# Mainboard.net
KiCad netlist of a schematic drawn in EAGLE
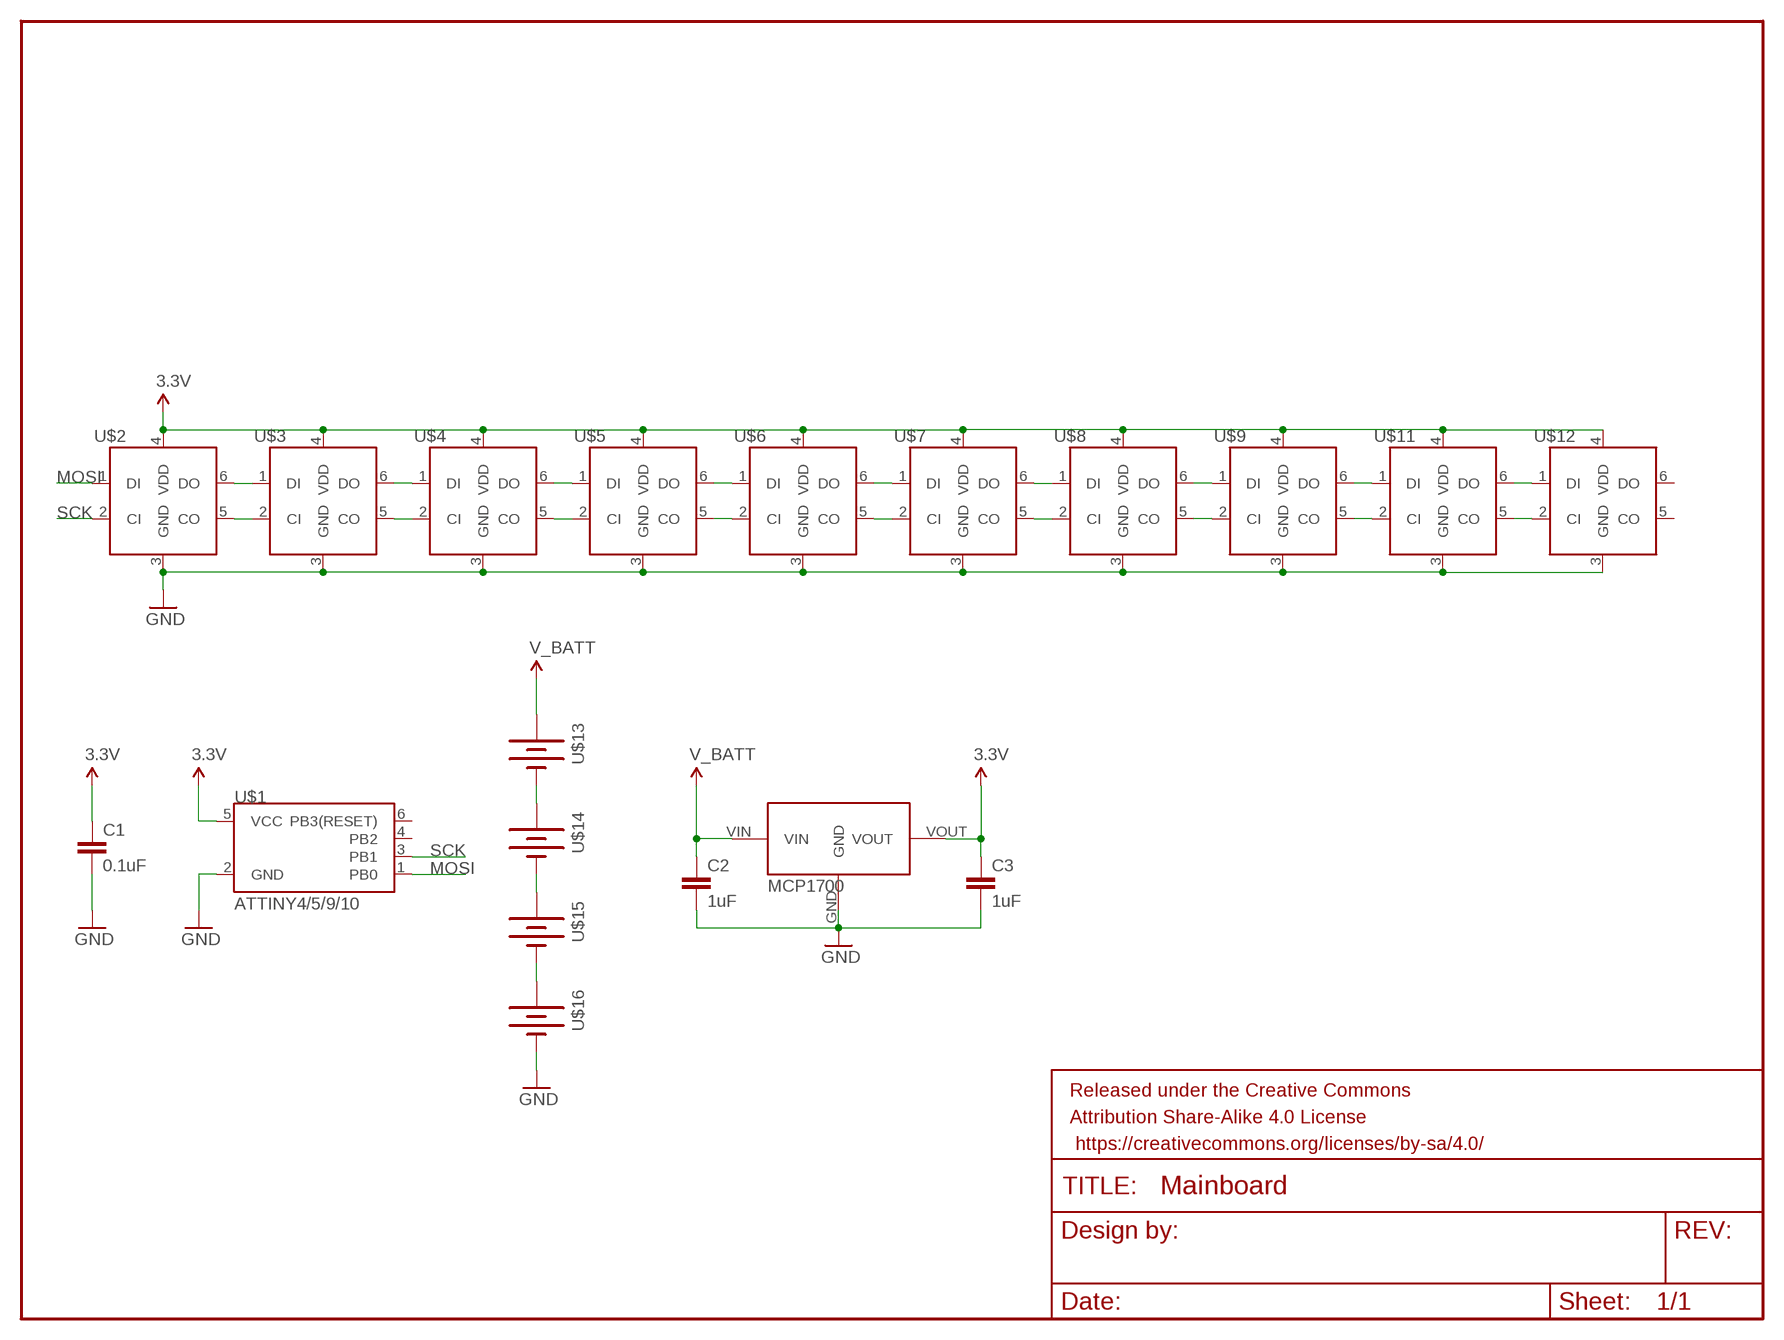
[diagram p0: schematic, sheet 1]

(export (version "E")
  (design (tool "Eeschema 10.0.6"))
  (components
    (comp (ref "C1")
      (value "0.1uF")
      (footprint "eagle-import:0402-CAP")
      (libsource (lib "eagle-import") (part "CAP0402-CAP"))
    )
    (comp (ref "C2")
      (value "1uF")
      (footprint "eagle-import:0402-CAP")
      (libsource (lib "eagle-import") (part "CAP0402-CAP"))
    )
    (comp (ref "C3")
      (value "1uF")
      (footprint "eagle-import:0402-CAP")
      (libsource (lib "eagle-import") (part "CAP0402-CAP"))
    )
    (comp (ref "FRAME1")
      (value "FRAME-LETTER")
      (footprint "eagle-import:CREATIVE_COMMONS")
      (libsource (lib "eagle-import") (part "FRAME-LETTER"))
    )
    (comp (ref "U$1")
      (value "ATTINY4/5/9/10")
      (footprint "eagle-import:SOT23-6")
      (libsource (lib "eagle-import") (part "ATTINY4/5/9/10"))
    )
    (comp (ref "U$2")
      (value "APA102C")
      (footprint "eagle-import:LED-TRICOLOR-5050-IC")
      (libsource (lib "eagle-import") (part "APA102C"))
    )
    (comp (ref "U$3")
      (value "APA102C")
      (footprint "eagle-import:LED-TRICOLOR-5050-IC")
      (libsource (lib "eagle-import") (part "APA102C"))
    )
    (comp (ref "U$4")
      (value "APA102C")
      (footprint "eagle-import:LED-TRICOLOR-5050-IC")
      (libsource (lib "eagle-import") (part "APA102C"))
    )
    (comp (ref "U$5")
      (value "APA102C")
      (footprint "eagle-import:LED-TRICOLOR-5050-IC")
      (libsource (lib "eagle-import") (part "APA102C"))
    )
    (comp (ref "U$6")
      (value "APA102C")
      (footprint "eagle-import:LED-TRICOLOR-5050-IC")
      (libsource (lib "eagle-import") (part "APA102C"))
    )
    (comp (ref "U$7")
      (value "APA102C")
      (footprint "eagle-import:LED-TRICOLOR-5050-IC")
      (libsource (lib "eagle-import") (part "APA102C"))
    )
    (comp (ref "U$8")
      (value "APA102C")
      (footprint "eagle-import:LED-TRICOLOR-5050-IC")
      (libsource (lib "eagle-import") (part "APA102C"))
    )
    (comp (ref "U$9")
      (value "APA102C")
      (footprint "eagle-import:LED-TRICOLOR-5050-IC")
      (libsource (lib "eagle-import") (part "APA102C"))
    )
    (comp (ref "U$11")
      (value "APA102C")
      (footprint "eagle-import:LED-TRICOLOR-5050-IC")
      (libsource (lib "eagle-import") (part "APA102C"))
    )
    (comp (ref "U$12")
      (value "APA102C")
      (footprint "eagle-import:LED-TRICOLOR-5050-IC")
      (libsource (lib "eagle-import") (part "APA102C"))
    )
    (comp (ref "U$13")
      (value "AAAA-BATTERYS")
      (footprint "eagle-import:KEYSTONE-SMD-AAAA-CLIPS")
      (libsource (lib "eagle-import") (part "AAAA-BATTERYS"))
    )
    (comp (ref "U$14")
      (value "AAAA-BATTERYS")
      (footprint "eagle-import:KEYSTONE-SMD-AAAA-CLIPS")
      (libsource (lib "eagle-import") (part "AAAA-BATTERYS"))
    )
    (comp (ref "U$15")
      (value "AAAA-BATTERYS")
      (footprint "eagle-import:KEYSTONE-SMD-AAAA-CLIPS")
      (libsource (lib "eagle-import") (part "AAAA-BATTERYS"))
    )
    (comp (ref "U$16")
      (value "AAAA-BATTERYS")
      (footprint "eagle-import:KEYSTONE-SMD-AAAA-CLIPS")
      (libsource (lib "eagle-import") (part "AAAA-BATTERYS"))
    )
    (comp (ref "U$17")
      (value "MCP1700")
      (footprint "eagle-import:MCP1700")
      (libsource (lib "eagle-import") (part "MCP1700"))
    )
  )
  (nets
    (net (code "1") (name "/MOSI") (class "Default")
      (node (ref "U$1") (pin "1") (pinfunction "PB0_1") (pintype "bidirectional"))
      (node (ref "U$2") (pin "1") (pinfunction "DI_1") (pintype "output"))
    )
    (net (code "2") (name "/SCK") (class "Default")
      (node (ref "U$1") (pin "3") (pinfunction "PB1_3") (pintype "bidirectional"))
      (node (ref "U$2") (pin "2") (pinfunction "CI_2") (pintype "output"))
    )
    (net (code "3") (name "3.3V") (class "Default")
      (node (ref "C1") (pin "1") (pinfunction "1_1") (pintype "passive"))
      (node (ref "C3") (pin "1") (pinfunction "1_1") (pintype "passive"))
      (node (ref "U$1") (pin "5") (pinfunction "VCC_5") (pintype "bidirectional"))
      (node (ref "U$11") (pin "4") (pinfunction "VDD_4") (pintype "power_in"))
      (node (ref "U$12") (pin "4") (pinfunction "VDD_4") (pintype "power_in"))
      (node (ref "U$17") (pin "VOUT") (pinfunction "VOUT_VOUT") (pintype "bidirectional"))
      (node (ref "U$2") (pin "4") (pinfunction "VDD_4") (pintype "power_in"))
      (node (ref "U$3") (pin "4") (pinfunction "VDD_4") (pintype "power_in"))
      (node (ref "U$4") (pin "4") (pinfunction "VDD_4") (pintype "power_in"))
      (node (ref "U$5") (pin "4") (pinfunction "VDD_4") (pintype "power_in"))
      (node (ref "U$6") (pin "4") (pinfunction "VDD_4") (pintype "power_in"))
      (node (ref "U$7") (pin "4") (pinfunction "VDD_4") (pintype "power_in"))
      (node (ref "U$8") (pin "4") (pinfunction "VDD_4") (pintype "power_in"))
      (node (ref "U$9") (pin "4") (pinfunction "VDD_4") (pintype "power_in"))
    )
    (net (code "4") (name "GND") (class "Default")
      (node (ref "C1") (pin "2") (pinfunction "2_2") (pintype "passive"))
      (node (ref "C2") (pin "2") (pinfunction "2_2") (pintype "passive"))
      (node (ref "C3") (pin "2") (pinfunction "2_2") (pintype "passive"))
      (node (ref "U$1") (pin "2") (pinfunction "GND_2") (pintype "bidirectional"))
      (node (ref "U$11") (pin "3") (pinfunction "GND_3") (pintype "power_in"))
      (node (ref "U$12") (pin "3") (pinfunction "GND_3") (pintype "power_in"))
      (node (ref "U$16") (pin "P$2") (pinfunction "-_P$2") (pintype "power_in"))
      (node (ref "U$17") (pin "GND") (pinfunction "GND_GND") (pintype "bidirectional"))
      (node (ref "U$2") (pin "3") (pinfunction "GND_3") (pintype "power_in"))
      (node (ref "U$3") (pin "3") (pinfunction "GND_3") (pintype "power_in"))
      (node (ref "U$4") (pin "3") (pinfunction "GND_3") (pintype "power_in"))
      (node (ref "U$5") (pin "3") (pinfunction "GND_3") (pintype "power_in"))
      (node (ref "U$6") (pin "3") (pinfunction "GND_3") (pintype "power_in"))
      (node (ref "U$7") (pin "3") (pinfunction "GND_3") (pintype "power_in"))
      (node (ref "U$8") (pin "3") (pinfunction "GND_3") (pintype "power_in"))
      (node (ref "U$9") (pin "3") (pinfunction "GND_3") (pintype "power_in"))
    )
    (net (code "5") (name "Net-(U$2-CO)") (class "Default")
      (node (ref "U$2") (pin "5") (pinfunction "CO_5") (pintype "input"))
      (node (ref "U$3") (pin "2") (pinfunction "CI_2") (pintype "output"))
    )
    (net (code "6") (name "Net-(U$2-DO)") (class "Default")
      (node (ref "U$2") (pin "6") (pinfunction "DO_6") (pintype "input"))
      (node (ref "U$3") (pin "1") (pinfunction "DI_1") (pintype "output"))
    )
    (net (code "7") (name "Net-(U$3-CO)") (class "Default")
      (node (ref "U$3") (pin "5") (pinfunction "CO_5") (pintype "input"))
      (node (ref "U$4") (pin "2") (pinfunction "CI_2") (pintype "output"))
    )
    (net (code "8") (name "Net-(U$3-DO)") (class "Default")
      (node (ref "U$3") (pin "6") (pinfunction "DO_6") (pintype "input"))
      (node (ref "U$4") (pin "1") (pinfunction "DI_1") (pintype "output"))
    )
    (net (code "9") (name "Net-(U$4-CO)") (class "Default")
      (node (ref "U$4") (pin "5") (pinfunction "CO_5") (pintype "input"))
      (node (ref "U$5") (pin "2") (pinfunction "CI_2") (pintype "output"))
    )
    (net (code "10") (name "Net-(U$4-DO)") (class "Default")
      (node (ref "U$4") (pin "6") (pinfunction "DO_6") (pintype "input"))
      (node (ref "U$5") (pin "1") (pinfunction "DI_1") (pintype "output"))
    )
    (net (code "11") (name "Net-(U$5-CO)") (class "Default")
      (node (ref "U$5") (pin "5") (pinfunction "CO_5") (pintype "input"))
      (node (ref "U$6") (pin "2") (pinfunction "CI_2") (pintype "output"))
    )
    (net (code "12") (name "Net-(U$5-DO)") (class "Default")
      (node (ref "U$5") (pin "6") (pinfunction "DO_6") (pintype "input"))
      (node (ref "U$6") (pin "1") (pinfunction "DI_1") (pintype "output"))
    )
    (net (code "13") (name "Net-(U$6-CO)") (class "Default")
      (node (ref "U$6") (pin "5") (pinfunction "CO_5") (pintype "input"))
      (node (ref "U$7") (pin "2") (pinfunction "CI_2") (pintype "output"))
    )
    (net (code "14") (name "Net-(U$6-DO)") (class "Default")
      (node (ref "U$6") (pin "6") (pinfunction "DO_6") (pintype "input"))
      (node (ref "U$7") (pin "1") (pinfunction "DI_1") (pintype "output"))
    )
    (net (code "15") (name "Net-(U$7-CO)") (class "Default")
      (node (ref "U$7") (pin "5") (pinfunction "CO_5") (pintype "input"))
      (node (ref "U$8") (pin "2") (pinfunction "CI_2") (pintype "output"))
    )
    (net (code "16") (name "Net-(U$7-DO)") (class "Default")
      (node (ref "U$7") (pin "6") (pinfunction "DO_6") (pintype "input"))
      (node (ref "U$8") (pin "1") (pinfunction "DI_1") (pintype "output"))
    )
    (net (code "17") (name "Net-(U$8-CO)") (class "Default")
      (node (ref "U$8") (pin "5") (pinfunction "CO_5") (pintype "input"))
      (node (ref "U$9") (pin "2") (pinfunction "CI_2") (pintype "output"))
    )
    (net (code "18") (name "Net-(U$8-DO)") (class "Default")
      (node (ref "U$8") (pin "6") (pinfunction "DO_6") (pintype "input"))
      (node (ref "U$9") (pin "1") (pinfunction "DI_1") (pintype "output"))
    )
    (net (code "19") (name "Net-(U$11-CI)") (class "Default")
      (node (ref "U$11") (pin "2") (pinfunction "CI_2") (pintype "output"))
      (node (ref "U$9") (pin "5") (pinfunction "CO_5") (pintype "input"))
    )
    (net (code "20") (name "Net-(U$11-CO)") (class "Default")
      (node (ref "U$11") (pin "5") (pinfunction "CO_5") (pintype "input"))
      (node (ref "U$12") (pin "2") (pinfunction "CI_2") (pintype "output"))
    )
    (net (code "21") (name "Net-(U$11-DI)") (class "Default")
      (node (ref "U$11") (pin "1") (pinfunction "DI_1") (pintype "output"))
      (node (ref "U$9") (pin "6") (pinfunction "DO_6") (pintype "input"))
    )
    (net (code "22") (name "Net-(U$11-DO)") (class "Default")
      (node (ref "U$11") (pin "6") (pinfunction "DO_6") (pintype "input"))
      (node (ref "U$12") (pin "1") (pinfunction "DI_1") (pintype "output"))
    )
    (net (code "23") (name "Net-(U$13--)") (class "Default")
      (node (ref "U$13") (pin "P$2") (pinfunction "-_P$2") (pintype "power_in"))
      (node (ref "U$14") (pin "P$1") (pinfunction "+_P$1") (pintype "power_in"))
    )
    (net (code "24") (name "Net-(U$14--)") (class "Default")
      (node (ref "U$14") (pin "P$2") (pinfunction "-_P$2") (pintype "power_in"))
      (node (ref "U$15") (pin "P$1") (pinfunction "+_P$1") (pintype "power_in"))
    )
    (net (code "25") (name "Net-(U$15--)") (class "Default")
      (node (ref "U$15") (pin "P$2") (pinfunction "-_P$2") (pintype "power_in"))
      (node (ref "U$16") (pin "P$1") (pinfunction "+_P$1") (pintype "power_in"))
    )
    (net (code "26") (name "V_BATT") (class "Default")
      (node (ref "C2") (pin "1") (pinfunction "1_1") (pintype "passive"))
      (node (ref "U$13") (pin "P$1") (pinfunction "+_P$1") (pintype "power_in"))
      (node (ref "U$17") (pin "VIN") (pinfunction "VIN_VIN") (pintype "bidirectional"))
    )
    (net (code "27") (name "unconnected-(U$1-PB2-Pad4)") (class "Default")
      (node (ref "U$1") (pin "4") (pinfunction "PB2_4") (pintype "bidirectional"))
    )
    (net (code "28") (name "unconnected-(U$1-PB3(RESET)-Pad6)") (class "Default")
      (node (ref "U$1") (pin "6") (pinfunction "PB3(RESET)_6") (pintype "bidirectional"))
    )
    (net (code "29") (name "unconnected-(U$12-CO-Pad5)") (class "Default")
      (node (ref "U$12") (pin "5") (pinfunction "CO_5") (pintype "input"))
    )
    (net (code "30") (name "unconnected-(U$12-DO-Pad6)") (class "Default")
      (node (ref "U$12") (pin "6") (pinfunction "DO_6") (pintype "input"))
    )
  )
)
